# TSC_AD7843_NEWLCD.net
KiCad netlist of a schematic drawn in Altium Designer
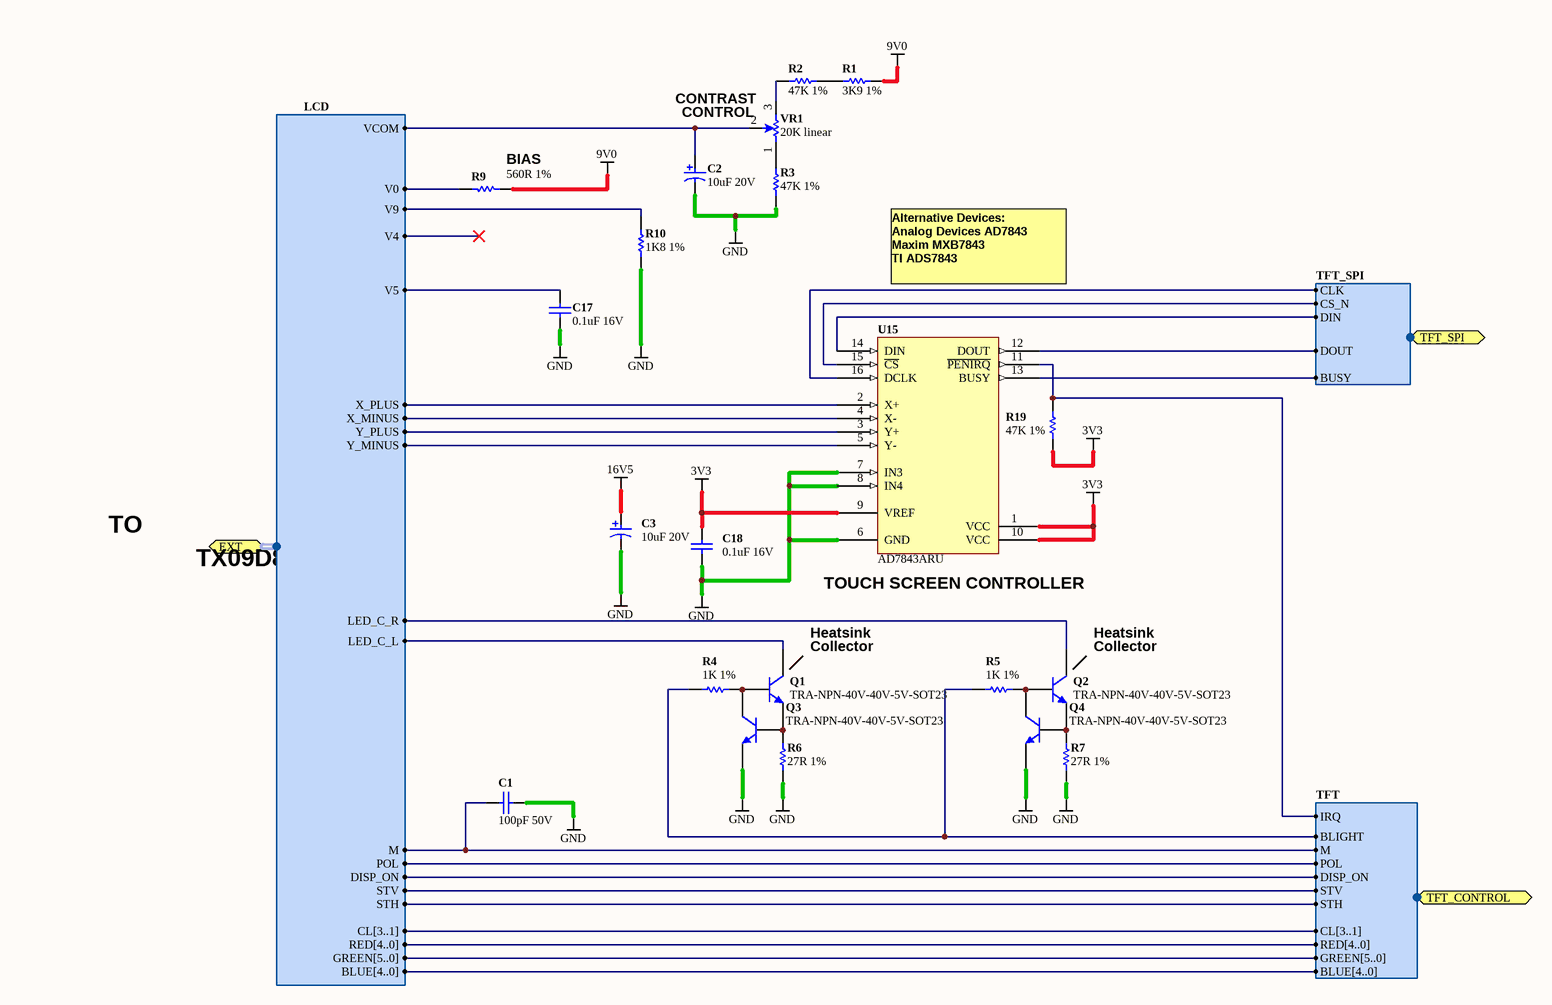
[diagram p0: TSC_AD7843_NEWLCD.SchDoc]

(export (version "E")
  (design (tool "Eeschema 10.0.6"))
  (components
    (comp (ref "C1")
      (value "100pF 50V")
      (footprint "CAPC1005-STAR")
      (description "Capacitor, Ceramic, 100pF 5% 50V 0402 (1005) COG")
      (fields (field (name "TOLERANCE") "5 %"))
      (libsource (lib "altium-import") (part "root_3_mirrored_CAP-NP_"))
    )
    (comp (ref "C2")
      (value "10uF 20V")
      (footprint "CAPC3528-STAR")
      (description "Capacitor, Tantalum, 10uF 10% 20V MCCT-B (3528)")
      (fields (field (name "TOLERANCE") "10 %"))
      (libsource (lib "altium-import") (part "root_0_CAP-P_"))
    )
    (comp (ref "C3")
      (value "10uF 20V")
      (footprint "CAPC3528-STAR")
      (description "Capacitor, Tantalum, 10uF 10% 20V MCCT-B (3528)")
      (fields (field (name "TOLERANCE") "10 %"))
      (libsource (lib "altium-import") (part "root_0_CAP-P_"))
    )
    (comp (ref "C17")
      (value "0.1uF 16V")
      (footprint "CAPC1005-STAR")
      (description "Capacitor, Ceramic, 0.1uF 10% 16V 0402 (1005) X7R")
      (fields (field (name "TOLERANCE") "10 %"))
      (libsource (lib "altium-import") (part "root_0_mirrored_CAP-NP_"))
    )
    (comp (ref "C18")
      (value "0.1uF 16V")
      (footprint "CAPC1005-STAR")
      (description "Capacitor, Ceramic, 0.1uF 10% 16V 0402 (1005) X7R")
      (fields (field (name "TOLERANCE") "10 %"))
      (libsource (lib "altium-import") (part "root_0_CAP-NP_"))
    )
    (comp (ref "Q1")
      (value "TRA-NPN-40V-40V-5V-SOT23")
      (footprint "SOT95P230-3C")
      (description "Transistor, FMMT491A Small Signal NPN")
      (libsource (lib "altium-import") (part "root_0_TRA-NPN_"))
    )
    (comp (ref "Q2")
      (value "TRA-NPN-40V-40V-5V-SOT23")
      (footprint "SOT95P230-3C")
      (description "Transistor, FMMT491A Small Signal NPN")
      (libsource (lib "altium-import") (part "root_0_TRA-NPN_"))
    )
    (comp (ref "Q3")
      (value "TRA-NPN-40V-40V-5V-SOT23")
      (footprint "SOT95P230-3C")
      (description "Transistor, FMMT491A Small Signal NPN")
      (libsource (lib "altium-import") (part "root_0_mirrored_TRA-NPN_"))
    )
    (comp (ref "Q4")
      (value "TRA-NPN-40V-40V-5V-SOT23")
      (footprint "SOT95P230-3C")
      (description "Transistor, FMMT491A Small Signal NPN")
      (libsource (lib "altium-import") (part "root_0_mirrored_TRA-NPN_"))
    )
    (comp (ref "R1")
      (value "3K9 1%")
      (footprint "RESC1005-STAR")
      (description "Resistor, 3K9 1% 0402 (1005)")
      (fields (field (name "TOLERANCE") "1 %"))
      (libsource (lib "altium-import") (part "root_1_RES_"))
    )
    (comp (ref "R2")
      (value "47K 1%")
      (footprint "RESC1005-STAR")
      (description "Resistor, 47K 1% 0402 (1005)")
      (fields (field (name "TOLERANCE") "1 %"))
      (libsource (lib "altium-import") (part "root_1_RES_"))
    )
    (comp (ref "R3")
      (value "47K 1%")
      (footprint "RESC1005-STAR")
      (description "Resistor, 47K 1% 0402 (1005)")
      (fields (field (name "TOLERANCE") "1 %"))
      (libsource (lib "altium-import") (part "root_2_RES_"))
    )
    (comp (ref "R4")
      (value "1K 1%")
      (footprint "RESC1005-STAR")
      (description "Resistor, 1K 1% 0402 (1005)")
      (fields (field (name "TOLERANCE") "1 %"))
      (libsource (lib "altium-import") (part "root_1_RES_"))
    )
    (comp (ref "R5")
      (value "1K 1%")
      (footprint "RESC1005-STAR")
      (description "Resistor, 1K 1% 0402 (1005)")
      (fields (field (name "TOLERANCE") "1 %"))
      (libsource (lib "altium-import") (part "root_1_RES_"))
    )
    (comp (ref "R6")
      (value "27R 1%")
      (footprint "RESC1005-STAR")
      (description "Resistor, 27R 1% 0402 (1005)")
      (fields (field (name "TOLERANCE") "1 %"))
      (libsource (lib "altium-import") (part "root_2_RES_"))
    )
    (comp (ref "R7")
      (value "27R 1%")
      (footprint "RESC1005-STAR")
      (description "Resistor, 27R 1% 0402 (1005)")
      (fields (field (name "TOLERANCE") "1 %"))
      (libsource (lib "altium-import") (part "root_2_RES_"))
    )
    (comp (ref "R9")
      (value "560R 1%")
      (footprint "RESC1005-STAR")
      (description "Resistor, 560R 1% 0402 (1005)")
      (fields (field (name "TOLERANCE") "1 %"))
      (libsource (lib "AltiumDesignLibrary") (part "RES"))
    )
    (comp (ref "R10")
      (value "1K8 1%")
      (footprint "RESC1005-STAR")
      (description "Resistor, 1K8 1% 0402 (1005)")
      (fields (field (name "TOLERANCE") "1 %"))
      (libsource (lib "AltiumDesignLibrary") (part "RES"))
    )
    (comp (ref "R19")
      (value "47K 1%")
      (footprint "RESC1005-STAR")
      (description "Resistor, 47K 1% 0402 (1005)")
      (fields (field (name "TOLERANCE") "1 %"))
      (libsource (lib "altium-import") (part "root_0_RES_"))
    )
    (comp (ref "U15")
      (value "AD7843ARU")
      (footprint "TSOP65P638-16")
      (description "AD7843ARU,12-bit SPI Touch Screen Digitizer")
      (libsource (lib "altium-import") (part "root_0_AD7843ARU_"))
    )
    (comp (ref "VR1")
      (value "20K linear")
      (footprint "TRIM_3314J-1-203E")
      (description "Potentiometer, 20K 4mm Cermet PCB SMT Trimmer")
      (libsource (lib "altium-import") (part "root_2_mirrored_POT_"))
    )
  )
  (nets
    (net (code "5") (name "/BLIGHT") (class "Default")
      (node (ref "R4") (pin "1") (pinfunction "1_1") (pintype "passive"))
      (node (ref "R5") (pin "1") (pinfunction "1_1") (pintype "passive"))
    )
    (net (code "6") (name "/BUSY") (class "Default")
      (node (ref "U15") (pin "13") (pinfunction "BUSY_13") (pintype "output"))
    )
    (net (code "7") (name "/CLK") (class "Default")
      (node (ref "U15") (pin "16") (pinfunction "DCLK_16") (pintype "input"))
    )
    (net (code "8") (name "/CS_N") (class "Default")
      (node (ref "U15") (pin "15") (pinfunction "~{CS}_15") (pintype "input"))
    )
    (net (code "9") (name "/DIN") (class "Default")
      (node (ref "U15") (pin "14") (pinfunction "DIN_14") (pintype "input"))
    )
    (net (code "11") (name "/DOUT") (class "Default")
      (node (ref "U15") (pin "12") (pinfunction "DOUT_12") (pintype "output"))
    )
    (net (code "13") (name "/IRQ") (class "Default")
      (node (ref "R19") (pin "1") (pinfunction "1_1") (pintype "passive"))
      (node (ref "U15") (pin "11") (pinfunction "~{PENIRQ}_11") (pintype "output"))
    )
    (net (code "14") (name "/LED_C_L") (class "Default")
      (node (ref "Q1") (pin "3") (pinfunction "C_3") (pintype "passive"))
    )
    (net (code "15") (name "/LED_C_R") (class "Default")
      (node (ref "Q2") (pin "3") (pinfunction "C_3") (pintype "passive"))
    )
    (net (code "16") (name "/M") (class "Default")
      (node (ref "C1") (pin "1") (pinfunction "1_1") (pintype "passive"))
    )
    (net (code "21") (name "/V0") (class "Default")
      (node (ref "R9") (pin "1") (pinfunction "1_1") (pintype "passive"))
    )
    (net (code "23") (name "/V5") (class "Default")
      (node (ref "C17") (pin "1") (pinfunction "1_1") (pintype "passive"))
    )
    (net (code "24") (name "/V9") (class "Default")
      (node (ref "R10") (pin "2") (pinfunction "2_2") (pintype "passive"))
    )
    (net (code "25") (name "/VCOM") (class "Default")
      (node (ref "C2") (pin "1") (pinfunction "1_1") (pintype "passive"))
      (node (ref "VR1") (pin "2") (pinfunction "2_2") (pintype "passive"))
    )
    (net (code "26") (name "/X_MINUS") (class "Default")
      (node (ref "U15") (pin "4") (pinfunction "X-_4") (pintype "input"))
    )
    (net (code "27") (name "/X_PLUS") (class "Default")
      (node (ref "U15") (pin "2") (pinfunction "X+_2") (pintype "input"))
    )
    (net (code "28") (name "/Y_MINUS") (class "Default")
      (node (ref "U15") (pin "5") (pinfunction "Y-_5") (pintype "input"))
    )
    (net (code "29") (name "/Y_PLUS") (class "Default")
      (node (ref "U15") (pin "3") (pinfunction "Y+_3") (pintype "input"))
    )
    (net (code "32") (name "3V3") (class "Default")
      (node (ref "C18") (pin "1") (pinfunction "1_1") (pintype "passive"))
      (node (ref "R19") (pin "2") (pinfunction "2_2") (pintype "passive"))
      (node (ref "U15") (pin "1") (pinfunction "VCC_1") (pintype "power_in"))
      (node (ref "U15") (pin "10") (pinfunction "VCC_10") (pintype "power_in"))
      (node (ref "U15") (pin "9") (pinfunction "VREF_9") (pintype "passive"))
    )
    (net (code "33") (name "9V0") (class "Default")
      (node (ref "R1") (pin "2") (pinfunction "2_2") (pintype "passive"))
      (node (ref "R9") (pin "2") (pinfunction "2_2") (pintype "passive"))
    )
    (net (code "34") (name "16V5") (class "Default")
      (node (ref "C3") (pin "1") (pinfunction "1_1") (pintype "passive"))
    )
    (net (code "35") (name "GND") (class "Default")
      (node (ref "C1") (pin "2") (pinfunction "2_2") (pintype "passive"))
      (node (ref "C17") (pin "2") (pinfunction "2_2") (pintype "passive"))
      (node (ref "C18") (pin "2") (pinfunction "2_2") (pintype "passive"))
      (node (ref "C2") (pin "2") (pinfunction "2_2") (pintype "passive"))
      (node (ref "C3") (pin "2") (pinfunction "2_2") (pintype "passive"))
      (node (ref "Q3") (pin "2") (pinfunction "E_2") (pintype "passive"))
      (node (ref "Q4") (pin "2") (pinfunction "E_2") (pintype "passive"))
      (node (ref "R10") (pin "1") (pinfunction "1_1") (pintype "passive"))
      (node (ref "R3") (pin "1") (pinfunction "1_1") (pintype "passive"))
      (node (ref "R6") (pin "1") (pinfunction "1_1") (pintype "passive"))
      (node (ref "R7") (pin "1") (pinfunction "1_1") (pintype "passive"))
      (node (ref "U15") (pin "6") (pinfunction "GND_6") (pintype "power_in"))
      (node (ref "U15") (pin "7") (pinfunction "IN3_7") (pintype "input"))
      (node (ref "U15") (pin "8") (pinfunction "IN4_8") (pintype "input"))
    )
    (net (code "36") (name "Net-(Q1-B)") (class "Default")
      (node (ref "Q1") (pin "1") (pinfunction "B_1") (pintype "passive"))
      (node (ref "Q3") (pin "3") (pinfunction "C_3") (pintype "passive"))
      (node (ref "R4") (pin "2") (pinfunction "2_2") (pintype "passive"))
    )
    (net (code "37") (name "Net-(Q1-E)") (class "Default")
      (node (ref "Q1") (pin "2") (pinfunction "E_2") (pintype "passive"))
      (node (ref "Q3") (pin "1") (pinfunction "B_1") (pintype "passive"))
      (node (ref "R6") (pin "2") (pinfunction "2_2") (pintype "passive"))
    )
    (net (code "38") (name "Net-(Q2-B)") (class "Default")
      (node (ref "Q2") (pin "1") (pinfunction "B_1") (pintype "passive"))
      (node (ref "Q4") (pin "3") (pinfunction "C_3") (pintype "passive"))
      (node (ref "R5") (pin "2") (pinfunction "2_2") (pintype "passive"))
    )
    (net (code "39") (name "Net-(Q2-E)") (class "Default")
      (node (ref "Q2") (pin "2") (pinfunction "E_2") (pintype "passive"))
      (node (ref "Q4") (pin "1") (pinfunction "B_1") (pintype "passive"))
      (node (ref "R7") (pin "2") (pinfunction "2_2") (pintype "passive"))
    )
    (net (code "40") (name "Net-(R1-Pad1)") (class "Default")
      (node (ref "R1") (pin "1") (pinfunction "1_1") (pintype "passive"))
      (node (ref "R2") (pin "2") (pinfunction "2_2") (pintype "passive"))
    )
    (net (code "41") (name "Net-(R2-Pad1)") (class "Default")
      (node (ref "R2") (pin "1") (pinfunction "1_1") (pintype "passive"))
      (node (ref "VR1") (pin "3") (pinfunction "3_3") (pintype "passive"))
    )
    (net (code "42") (name "Net-(R3-Pad2)") (class "Default")
      (node (ref "R3") (pin "2") (pinfunction "2_2") (pintype "passive"))
      (node (ref "VR1") (pin "1") (pinfunction "1_1") (pintype "passive"))
    )
  )
)
